# maus.net
KiCad netlist of a schematic drawn in EAGLE
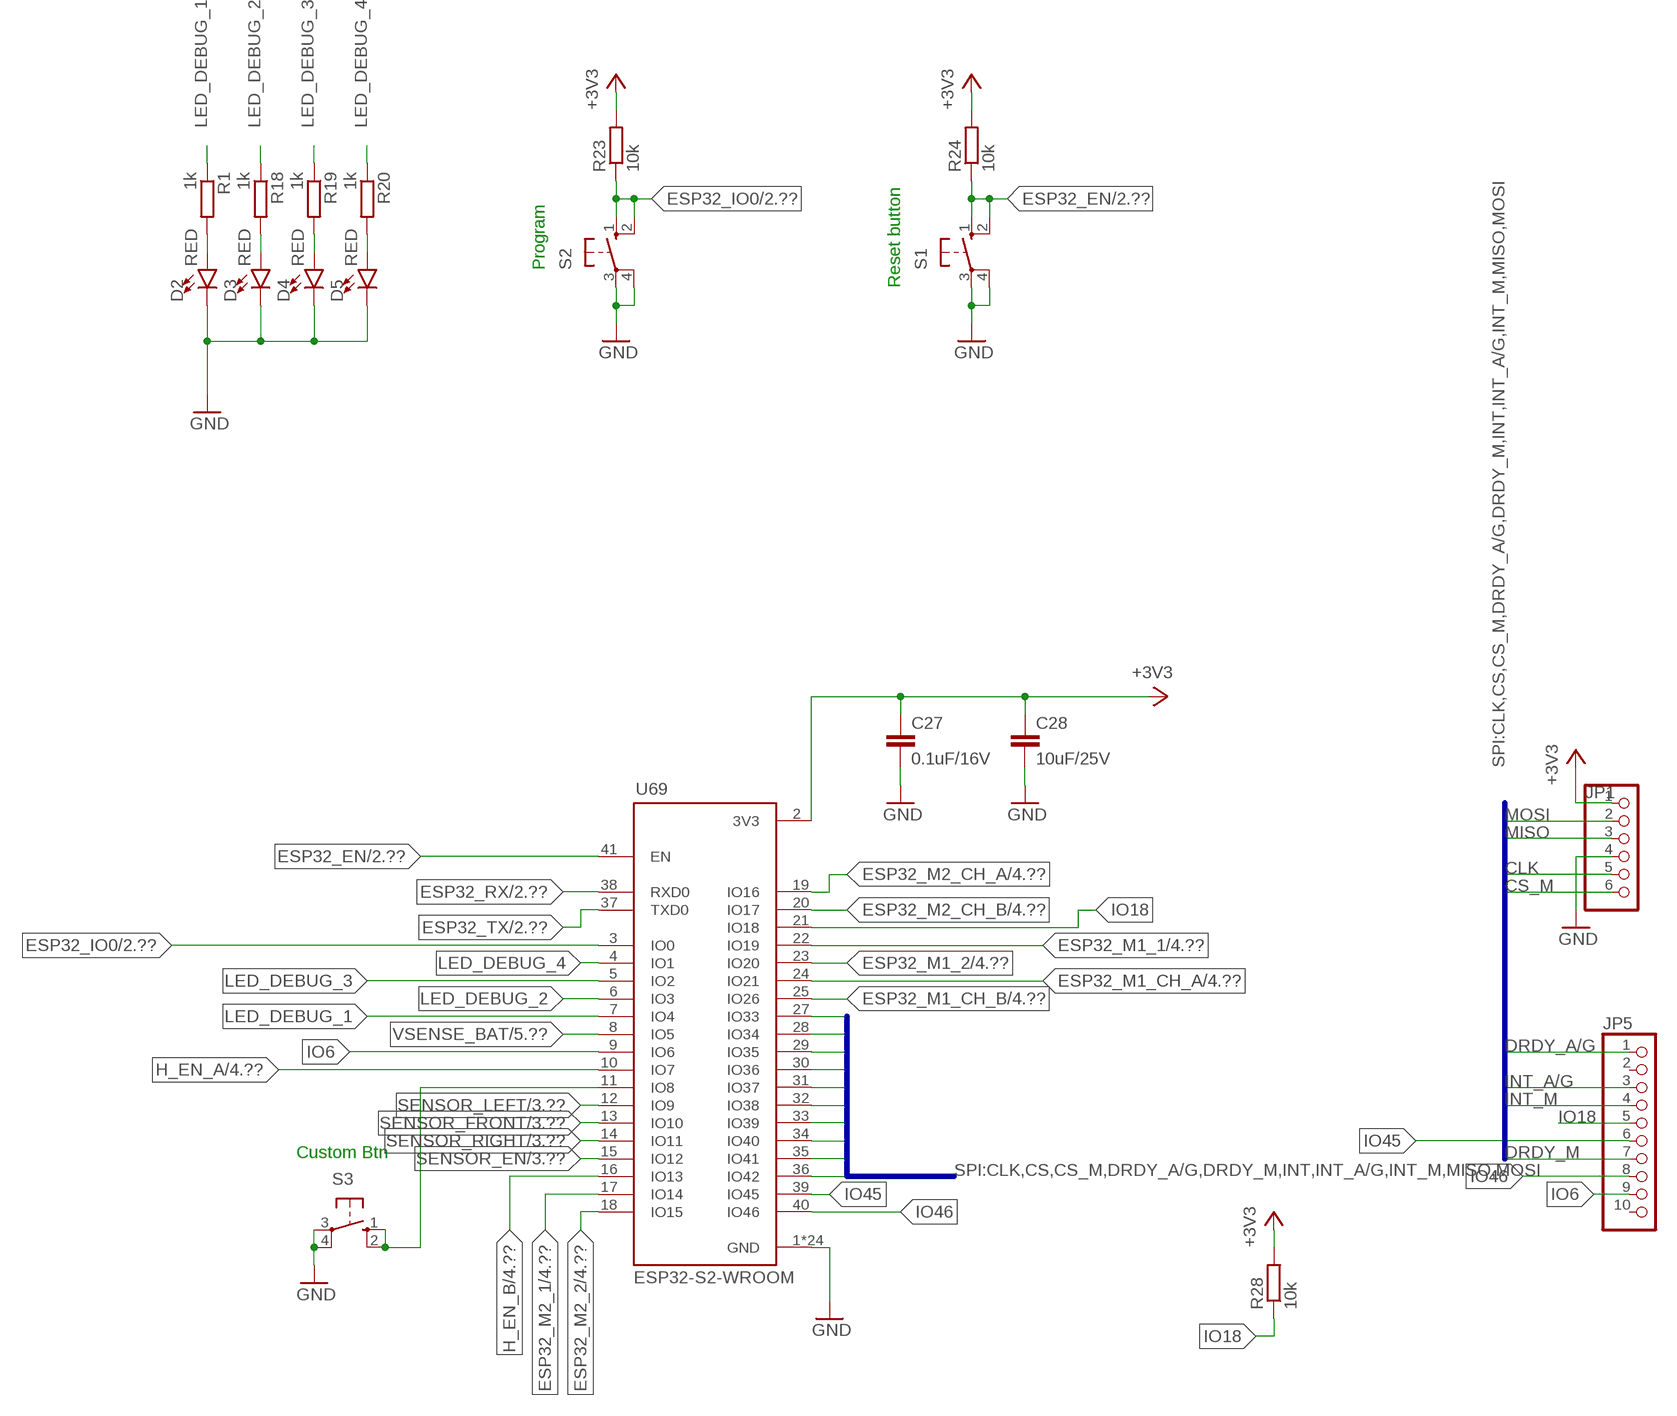
[diagram p0: schematic, sheet 1]
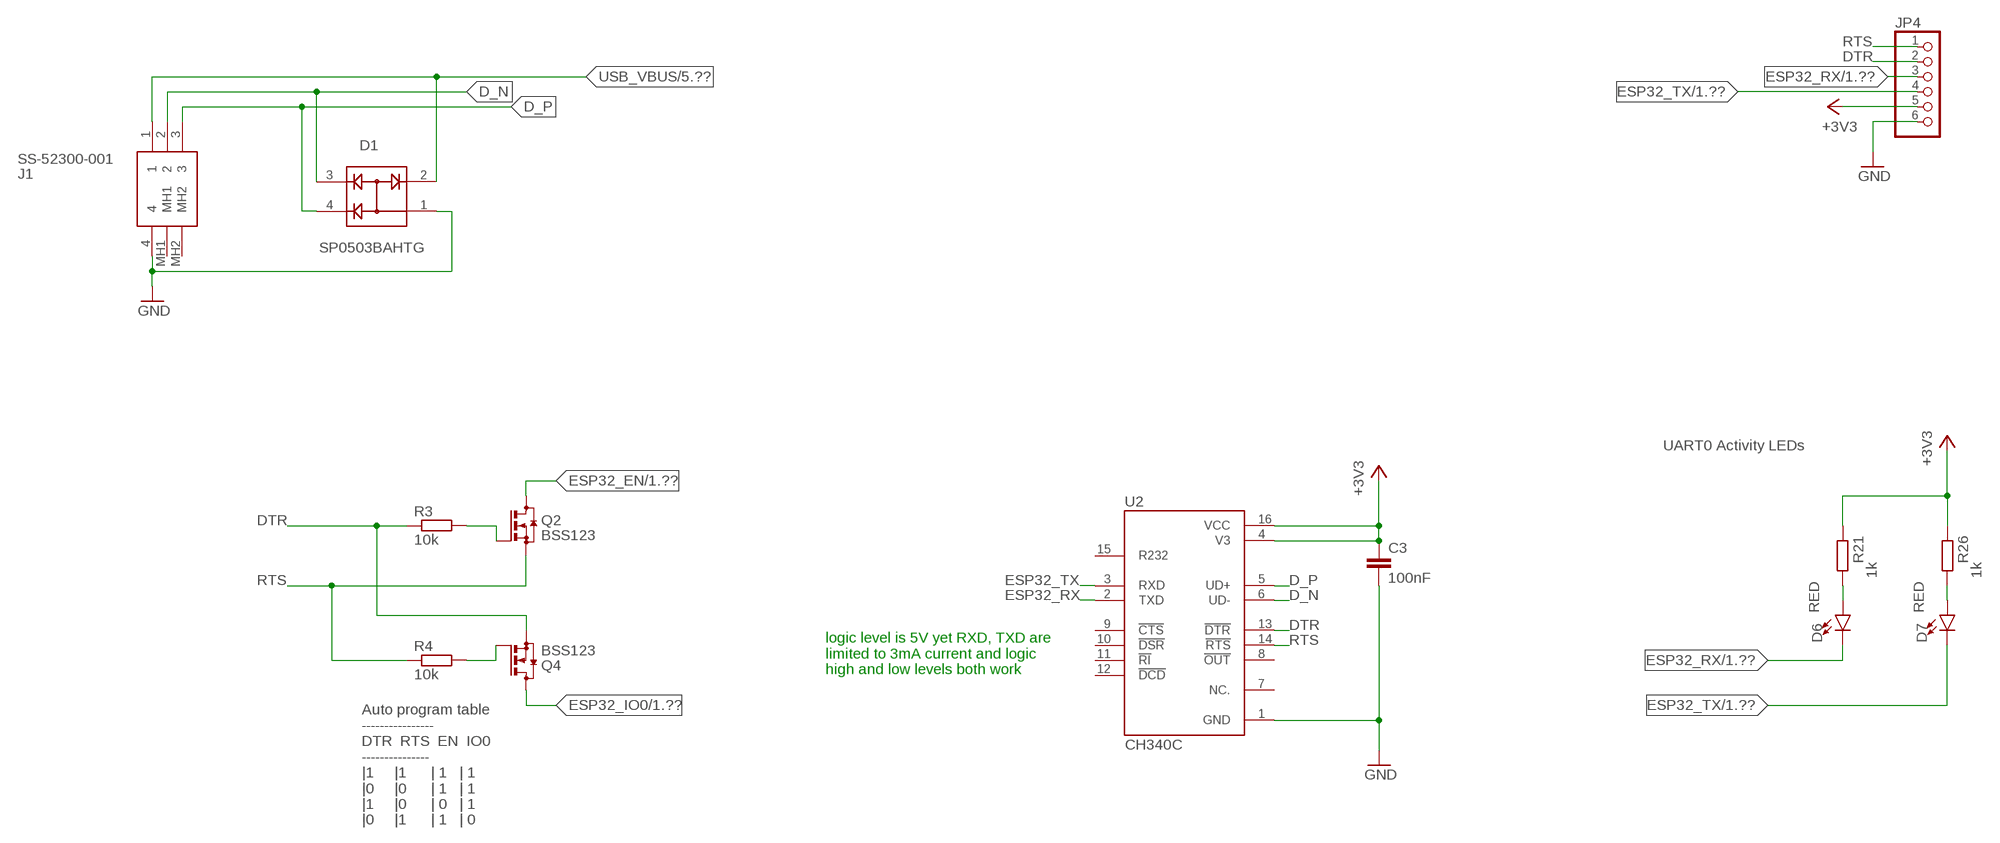
[diagram p1: schematic, sheet 2]
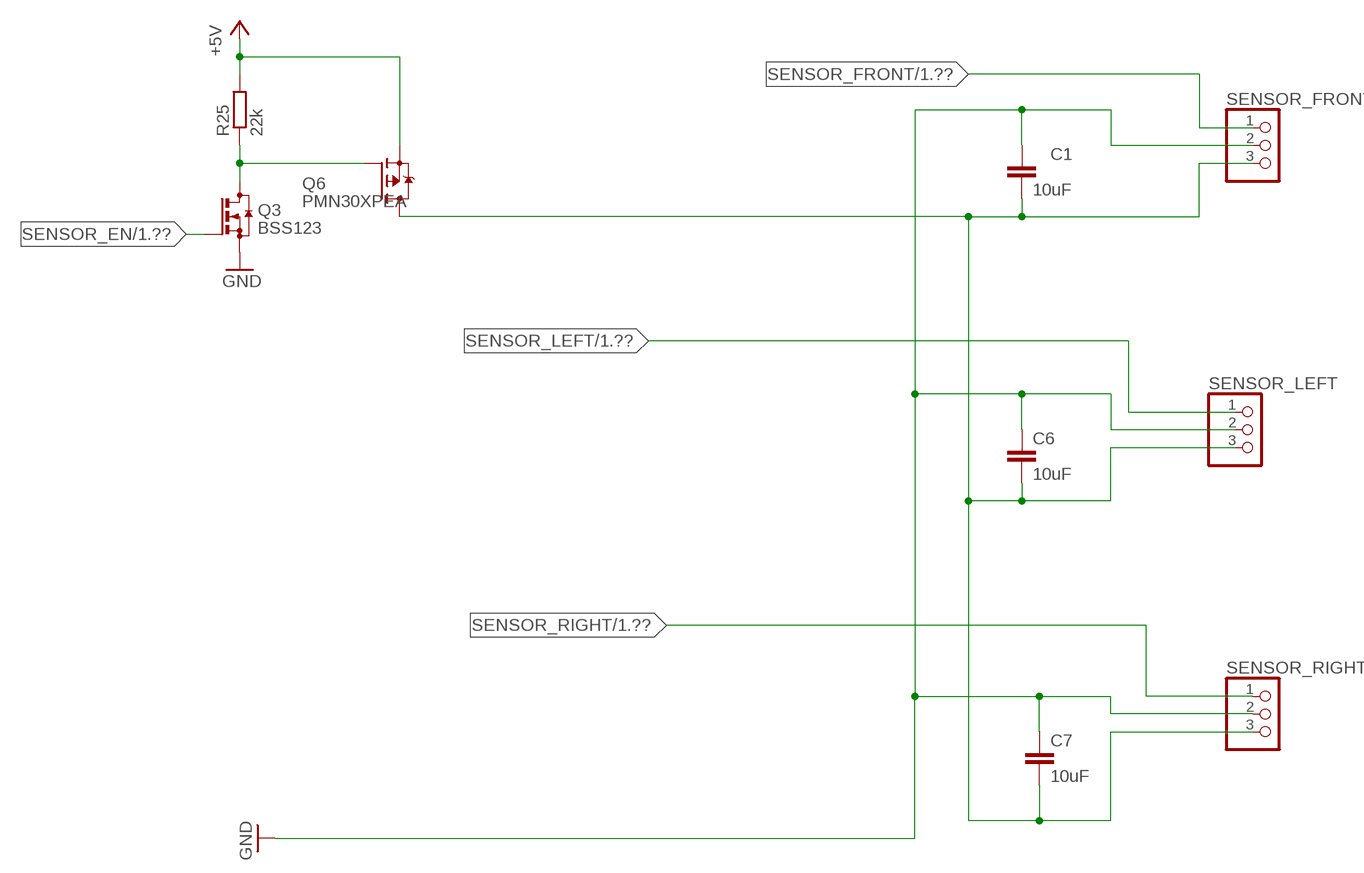
[diagram p2: schematic, sheet 3]
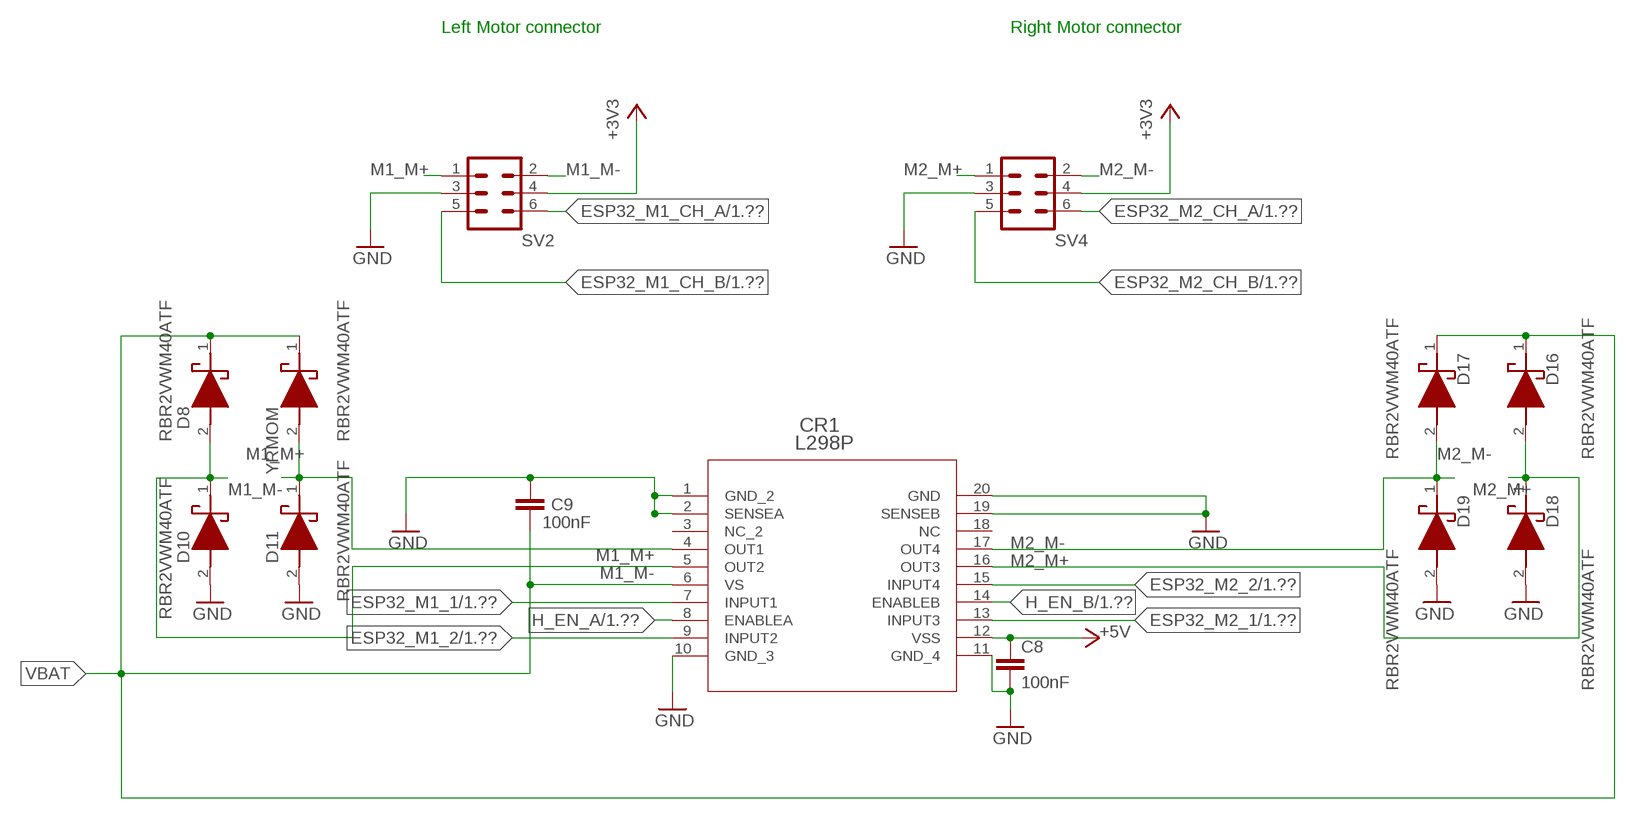
[diagram p3: schematic, sheet 4]
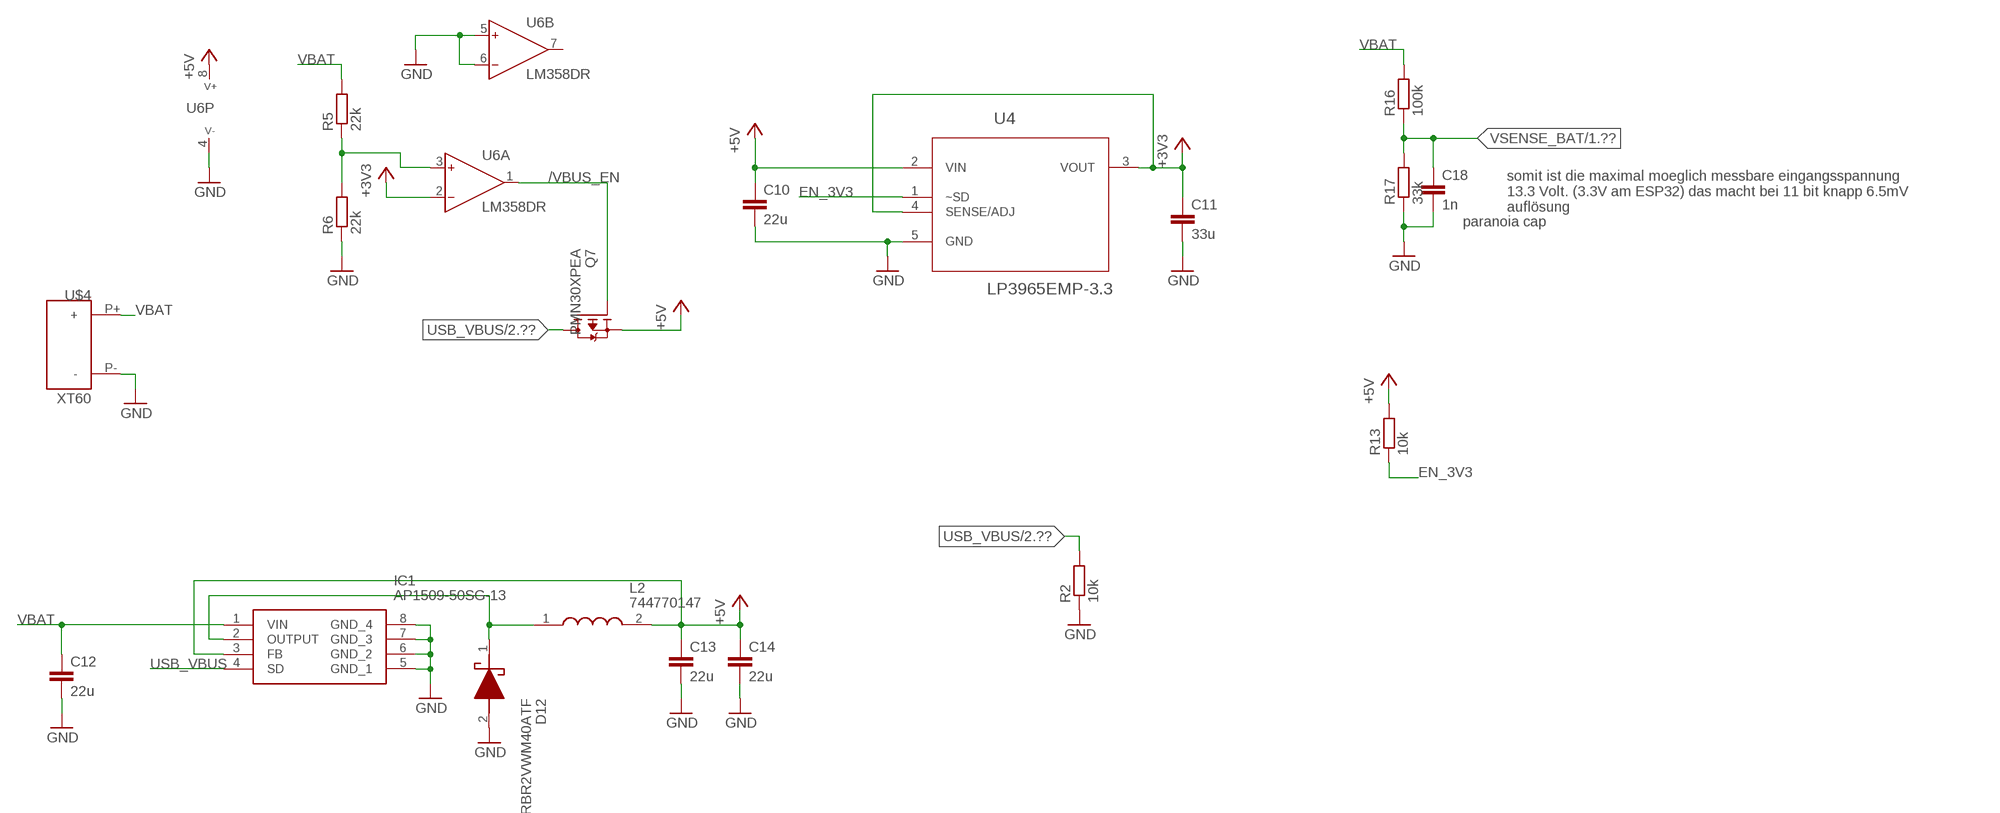
[diagram p4: schematic, sheet 5]
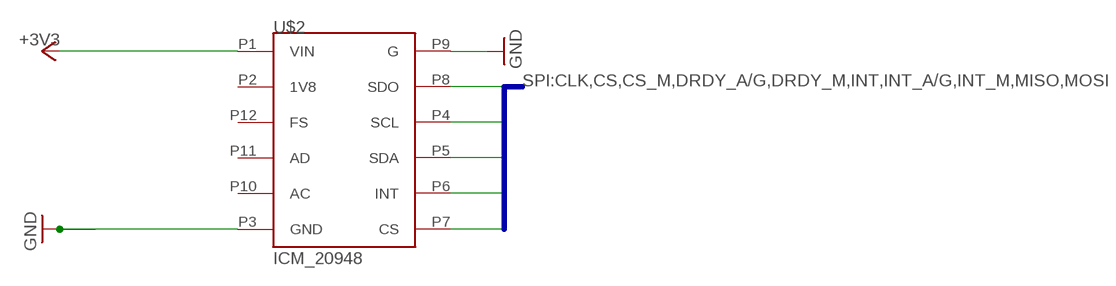
[diagram p5: schematic, sheet 6]

(export (version "E")
  (design (tool "Eeschema 10.0.6"))
  (components
    (comp (ref "C27")
      (value "0.1uF/16V")
      (footprint "eagle-import:C0805")
      (libsource (lib "eagle-import") (part "C-EUC0805"))
    )
    (comp (ref "C28")
      (value "10uF/25V")
      (footprint "eagle-import:C0805")
      (libsource (lib "eagle-import") (part "C-EUC0805"))
    )
    (comp (ref "D2")
      (value "RED")
      (footprint "eagle-import:LED-1206")
      (libsource (lib "eagle-import") (part "LED-RED1206"))
    )
    (comp (ref "D3")
      (value "RED")
      (footprint "eagle-import:LED-1206")
      (libsource (lib "eagle-import") (part "LED-RED1206"))
    )
    (comp (ref "D4")
      (value "RED")
      (footprint "eagle-import:LED-1206")
      (libsource (lib "eagle-import") (part "LED-RED1206"))
    )
    (comp (ref "D5")
      (value "RED")
      (footprint "eagle-import:LED-1206")
      (libsource (lib "eagle-import") (part "LED-RED1206"))
    )
    (comp (ref "JP1")
      (value "PINHD-1X6")
      (footprint "eagle-import:1X06")
      (libsource (lib "eagle-import") (part "PINHD-1X6"))
    )
    (comp (ref "JP5")
      (value "PINHD-1X10")
      (footprint "eagle-import:1X10")
      (libsource (lib "eagle-import") (part "PINHD-1X10"))
    )
    (comp (ref "R1")
      (value "1k")
      (footprint "eagle-import:R0805")
      (libsource (lib "eagle-import") (part "R-EU_R0805"))
    )
    (comp (ref "R18")
      (value "1k")
      (footprint "eagle-import:R0805")
      (libsource (lib "eagle-import") (part "R-EU_R0805"))
    )
    (comp (ref "R19")
      (value "1k")
      (footprint "eagle-import:R0805")
      (libsource (lib "eagle-import") (part "R-EU_R0805"))
    )
    (comp (ref "R20")
      (value "1k")
      (footprint "eagle-import:R0805")
      (libsource (lib "eagle-import") (part "R-EU_R0805"))
    )
    (comp (ref "R23")
      (value "10k")
      (footprint "eagle-import:R0805")
      (libsource (lib "eagle-import") (part "R-EU_R0805"))
    )
    (comp (ref "R24")
      (value "10k")
      (footprint "eagle-import:R0805")
      (libsource (lib "eagle-import") (part "R-EU_R0805"))
    )
    (comp (ref "R28")
      (value "10k")
      (footprint "eagle-import:R0805")
      (libsource (lib "eagle-import") (part "R-EU_R0805"))
    )
    (comp (ref "S1")
      (value "10-XX")
      (footprint "eagle-import:B3F-10XX")
      (fields (field (name "MPN") "B3F-1000"))
      (libsource (lib "eagle-import") (part "10-XX"))
    )
    (comp (ref "S2")
      (value "10-XX")
      (footprint "eagle-import:B3F-10XX")
      (fields (field (name "MPN") "B3F-1000"))
      (libsource (lib "eagle-import") (part "10-XX"))
    )
    (comp (ref "S3")
      (value "10-XX")
      (footprint "eagle-import:B3F-10XX")
      (fields (field (name "MPN") "B3F-1000"))
      (libsource (lib "eagle-import") (part "10-XX"))
    )
    (comp (ref "U69")
      (value "ESP32-S2-WROOM")
      (footprint "eagle-import:XCVR_ESP32-S2-WROOM")
      (fields (field (name "MF") "Espressif Systems"))
      (libsource (lib "eagle-import") (part "ESP32-S2-WROOM"))
    )
    (comp (ref "C8")
      (value "100nF")
      (footprint "eagle-import:C0805")
      (libsource (lib "eagle-import") (part "C-EUC0805"))
    )
    (comp (ref "C9")
      (value "100nF")
      (footprint "eagle-import:C0805")
      (libsource (lib "eagle-import") (part "C-EUC0805"))
    )
    (comp (ref "CR1")
      (value "L298P")
      (footprint "eagle-import:POWERSO-20_STM")
      (fields (field (name "COPYRIGHT") "Copyright (C) 2022 Ultra Librarian. All rights reserved."))
      (libsource (lib "eagle-import") (part "L298P"))
    )
    (comp (ref "D8")
      (value "RBR2VWM40ATF")
      (footprint "eagle-import:RB068VWM100")
      (libsource (lib "eagle-import") (part "RBR2VWM40ATF"))
    )
    (comp (ref "D10")
      (value "RBR2VWM40ATF")
      (footprint "eagle-import:RB068VWM100")
      (libsource (lib "eagle-import") (part "RBR2VWM40ATF"))
    )
    (comp (ref "D11")
      (value "RBR2VWM40ATF")
      (footprint "eagle-import:RB068VWM100")
      (libsource (lib "eagle-import") (part "RBR2VWM40ATF"))
    )
    (comp (ref "D16")
      (value "RBR2VWM40ATF")
      (footprint "eagle-import:RB068VWM100")
      (libsource (lib "eagle-import") (part "RBR2VWM40ATF"))
    )
    (comp (ref "D17")
      (value "RBR2VWM40ATF")
      (footprint "eagle-import:RB068VWM100")
      (libsource (lib "eagle-import") (part "RBR2VWM40ATF"))
    )
    (comp (ref "D18")
      (value "RBR2VWM40ATF")
      (footprint "eagle-import:RB068VWM100")
      (libsource (lib "eagle-import") (part "RBR2VWM40ATF"))
    )
    (comp (ref "D19")
      (value "RBR2VWM40ATF")
      (footprint "eagle-import:RB068VWM100")
      (libsource (lib "eagle-import") (part "RBR2VWM40ATF"))
    )
    (comp (ref "SV2")
      (value "ML6")
      (footprint "eagle-import:ML6")
      (libsource (lib "eagle-import") (part "ML6"))
    )
    (comp (ref "SV4")
      (value "ML6")
      (footprint "eagle-import:ML6")
      (libsource (lib "eagle-import") (part "ML6"))
    )
    (comp (ref "YRMOM")
      (value "RBR2VWM40ATF")
      (footprint "eagle-import:RB068VWM100")
      (libsource (lib "eagle-import") (part "RBR2VWM40ATF"))
    )
    (comp (ref "C3")
      (value "100nF")
      (footprint "eagle-import:C0805")
      (libsource (lib "eagle-import") (part "C-EUC0805"))
    )
    (comp (ref "D1")
      (value "SP0503BAHTG")
      (footprint "eagle-import:SOT143")
      (fields (field (name "MF") "Littelfuse Inc."))
      (libsource (lib "eagle-import") (part "SP0503BAHTG"))
    )
    (comp (ref "D6")
      (value "RED")
      (footprint "eagle-import:LED-1206")
      (libsource (lib "eagle-import") (part "LED-RED1206"))
    )
    (comp (ref "D7")
      (value "RED")
      (footprint "eagle-import:LED-1206")
      (libsource (lib "eagle-import") (part "LED-RED1206"))
    )
    (comp (ref "J1")
      (value "SS-52300-001")
      (footprint "eagle-import:SS52300001")
      (fields (field (name "MOUSER_PART_NUMBER") "530-SS-52300-001"))
      (libsource (lib "eagle-import") (part "SS-52300-001"))
    )
    (comp (ref "JP4")
      (value "PINHD-1X6")
      (footprint "eagle-import:1X06")
      (libsource (lib "eagle-import") (part "PINHD-1X6"))
    )
    (comp (ref "Q2")
      (value "BSS123")
      (footprint "eagle-import:SOT23")
      (libsource (lib "eagle-import") (part "BSS123"))
    )
    (comp (ref "Q4")
      (value "BSS123")
      (footprint "eagle-import:SOT23")
      (libsource (lib "eagle-import") (part "BSS123"))
    )
    (comp (ref "R3")
      (value "10k")
      (footprint "eagle-import:R0805")
      (libsource (lib "eagle-import") (part "R-EU_R0805"))
    )
    (comp (ref "R4")
      (value "10k")
      (footprint "eagle-import:R0805")
      (libsource (lib "eagle-import") (part "R-EU_R0805"))
    )
    (comp (ref "R21")
      (value "1k")
      (footprint "eagle-import:R0805")
      (libsource (lib "eagle-import") (part "R-EU_R0805"))
    )
    (comp (ref "R26")
      (value "1k")
      (footprint "eagle-import:R0805")
      (libsource (lib "eagle-import") (part "R-EU_R0805"))
    )
    (comp (ref "U2")
      (value "CH340C")
      (footprint "eagle-import:SOIC127P600X180-16N")
      (fields (field (name "MF") "WCH"))
      (libsource (lib "eagle-import") (part "CH340C"))
    )
    (comp (ref "C1")
      (value "10uF")
      (footprint "eagle-import:C0805")
      (libsource (lib "eagle-import") (part "C-EUC0805"))
    )
    (comp (ref "C6")
      (value "10uF")
      (footprint "eagle-import:C0805")
      (libsource (lib "eagle-import") (part "C-EUC0805"))
    )
    (comp (ref "C7")
      (value "10uF")
      (footprint "eagle-import:C0805")
      (libsource (lib "eagle-import") (part "C-EUC0805"))
    )
    (comp (ref "Q3")
      (value "BSS123")
      (footprint "eagle-import:SOT23")
      (libsource (lib "eagle-import") (part "BSS123"))
    )
    (comp (ref "Q6")
      (value "PMN30XPEA")
      (footprint "eagle-import:SOT95P255X110-6N")
      (libsource (lib "eagle-import") (part "PMN30XPEA"))
    )
    (comp (ref "R25")
      (value "22k")
      (footprint "eagle-import:R0805")
      (libsource (lib "eagle-import") (part "R-EU_R0805"))
    )
    (comp (ref "SENSOR_FRONT")
      (value "PINHD-1X3")
      (footprint "eagle-import:1X03")
      (libsource (lib "eagle-import") (part "PINHD-1X3"))
    )
    (comp (ref "SENSOR_LEFT")
      (value "PINHD-1X3")
      (footprint "eagle-import:1X03")
      (libsource (lib "eagle-import") (part "PINHD-1X3"))
    )
    (comp (ref "SENSOR_RIGHT")
      (value "PINHD-1X3")
      (footprint "eagle-import:1X03")
      (libsource (lib "eagle-import") (part "PINHD-1X3"))
    )
    (comp (ref "C10")
      (value "22u")
      (footprint "eagle-import:C0805")
      (libsource (lib "eagle-import") (part "C-EUC0805"))
    )
    (comp (ref "C11")
      (value "33u")
      (footprint "eagle-import:C0805")
      (libsource (lib "eagle-import") (part "C-EUC0805"))
    )
    (comp (ref "C12")
      (value "22u")
      (footprint "eagle-import:C0805")
      (libsource (lib "eagle-import") (part "C-EUC0805"))
    )
    (comp (ref "C13")
      (value "22u")
      (footprint "eagle-import:C0805")
      (libsource (lib "eagle-import") (part "C-EUC0805"))
    )
    (comp (ref "C14")
      (value "22u")
      (footprint "eagle-import:C0805")
      (libsource (lib "eagle-import") (part "C-EUC0805"))
    )
    (comp (ref "C18")
      (value "1n")
      (footprint "eagle-import:C0805")
      (libsource (lib "eagle-import") (part "C-EUC0805"))
    )
    (comp (ref "D12")
      (value "RBR2VWM40ATF")
      (footprint "eagle-import:RB068VWM100")
      (libsource (lib "eagle-import") (part "RBR2VWM40ATF"))
    )
    (comp (ref "IC1")
      (value "AP1509-50SG-13")
      (footprint "eagle-import:SOIC127P600X175-8N")
      (fields (field (name "MOUSER_PART_NUMBER") "621-AP1509-50SG-13"))
      (libsource (lib "eagle-import") (part "AP1509-50SG-13"))
    )
    (comp (ref "L2")
      (value "744770147")
      (footprint "eagle-import:WE-PD_1260_1245_1280_121054")
      (fields (field (name "MOUSER_PART_NUMBER") "710-744770147"))
      (libsource (lib "eagle-import") (part "744770147"))
    )
    (comp (ref "Q7")
      (value "PMN30XPEA")
      (footprint "eagle-import:SOT95P255X110-6N")
      (libsource (lib "eagle-import") (part "PMN30XPEA"))
    )
    (comp (ref "R2")
      (value "10k")
      (footprint "eagle-import:R0805")
      (libsource (lib "eagle-import") (part "R-EU_R0805"))
    )
    (comp (ref "R5")
      (value "22k")
      (footprint "eagle-import:R0805")
      (libsource (lib "eagle-import") (part "R-EU_R0805"))
    )
    (comp (ref "R6")
      (value "22k")
      (footprint "eagle-import:R0805")
      (libsource (lib "eagle-import") (part "R-EU_R0805"))
    )
    (comp (ref "R13")
      (value "10k")
      (footprint "eagle-import:R0805")
      (libsource (lib "eagle-import") (part "R-EU_R0805"))
    )
    (comp (ref "R16")
      (value "100k")
      (footprint "eagle-import:R0805")
      (libsource (lib "eagle-import") (part "R-EU_R0805"))
    )
    (comp (ref "R17")
      (value "33k")
      (footprint "eagle-import:R0805")
      (libsource (lib "eagle-import") (part "R-EU_R0805"))
    )
    (comp (ref "U$4")
      (value "XT60")
      (footprint "eagle-import:XT60-UPRIGHT")
      (libsource (lib "eagle-import") (part "XT60"))
    )
    (comp (ref "U4")
      (value "LP3965EMP-3.3")
      (footprint "eagle-import:SOT150P696X180-5N")
      (fields (field (name "MF") "Texas Instruments") (field (name "MP") "LP3965EMP-3.3/NOPB"))
      (libsource (lib "eagle-import") (part "LP3965EMP-3.3"))
    )
    (comp (ref "U6")
      (value "LM358DR")
      (footprint "eagle-import:SOIC127P610X175-8N")
      (libsource (lib "eagle-import") (part "LM358DR"))
    )
    (comp (ref "U$2")
      (value "ICM_20948")
      (footprint "eagle-import:ICM_20948-F")
      (libsource (lib "eagle-import") (part "ICM_20948"))
    )
  )
  (nets
    (net (code "8") (name "+3V3") (class "Default")
      (node (ref "C11") (pin "1") (pinfunction "1_1") (pintype "passive"))
      (node (ref "C27") (pin "1") (pinfunction "1_1") (pintype "passive"))
      (node (ref "C28") (pin "1") (pinfunction "1_1") (pintype "passive"))
      (node (ref "C3") (pin "1") (pinfunction "1_1") (pintype "passive"))
      (node (ref "JP1") (pin "1") (pinfunction "1_1") (pintype "passive"))
      (node (ref "JP4") (pin "5") (pinfunction "5_5") (pintype "passive"))
      (node (ref "R21") (pin "2") (pinfunction "2_2") (pintype "passive"))
      (node (ref "R23") (pin "2") (pinfunction "2_2") (pintype "passive"))
      (node (ref "R24") (pin "2") (pinfunction "2_2") (pintype "passive"))
      (node (ref "R26") (pin "2") (pinfunction "2_2") (pintype "passive"))
      (node (ref "R28") (pin "2") (pinfunction "2_2") (pintype "passive"))
      (node (ref "SV2") (pin "4") (pinfunction "4_4") (pintype "passive"))
      (node (ref "SV4") (pin "4") (pinfunction "4_4") (pintype "passive"))
      (node (ref "U$2") (pin "P1") (pinfunction "VIN_P1") (pintype "bidirectional"))
      (node (ref "U2") (pin "16") (pinfunction "VCC_16") (pintype "power_in"))
      (node (ref "U2") (pin "4") (pinfunction "V3_4") (pintype "power_in"))
      (node (ref "U4") (pin "3") (pinfunction "VOUT_3") (pintype "passive"))
      (node (ref "U4") (pin "4") (pinfunction "SENSE/ADJ_4") (pintype "input"))
      (node (ref "U6") (pin "2") (pinfunction "IN-_2") (pintype "input"))
      (node (ref "U69") (pin "2") (pinfunction "3V3_2") (pintype "power_in"))
    )
    (net (code "9") (name "+5V") (class "Default")
      (node (ref "C10") (pin "1") (pinfunction "1_1") (pintype "passive"))
      (node (ref "C13") (pin "1") (pinfunction "1_1") (pintype "passive"))
      (node (ref "C14") (pin "1") (pinfunction "1_1") (pintype "passive"))
      (node (ref "C8") (pin "1") (pinfunction "1_1") (pintype "passive"))
      (node (ref "CR1") (pin "12") (pinfunction "VSS_12") (pintype "power_in"))
      (node (ref "IC1") (pin "3") (pinfunction "FB_3") (pintype "bidirectional"))
      (node (ref "L2") (pin "2") (pinfunction "2_2") (pintype "bidirectional"))
      (node (ref "Q6") (pin "4") (pinfunction "S_4") (pintype "passive"))
      (node (ref "Q7") (pin "4") (pinfunction "S_4") (pintype "passive"))
      (node (ref "R13") (pin "2") (pinfunction "2_2") (pintype "passive"))
      (node (ref "R25") (pin "2") (pinfunction "2_2") (pintype "passive"))
      (node (ref "U4") (pin "2") (pinfunction "VIN_2") (pintype "input"))
      (node (ref "U6") (pin "8") (pinfunction "V+_8") (pintype "power_in"))
    )
    (net (code "12") (name "CLK") (class "Default")
      (node (ref "JP1") (pin "5") (pinfunction "5_5") (pintype "passive"))
      (node (ref "U$2") (pin "P4") (pinfunction "SCL_P4") (pintype "bidirectional"))
      (node (ref "U69") (pin "30") (pinfunction "IO36_30") (pintype "bidirectional"))
    )
    (net (code "13") (name "CS") (class "Default")
      (node (ref "U$2") (pin "P7") (pinfunction "CS_P7") (pintype "bidirectional"))
      (node (ref "U69") (pin "28") (pinfunction "IO34_28") (pintype "bidirectional"))
    )
    (net (code "14") (name "CS_M") (class "Default")
      (node (ref "JP1") (pin "6") (pinfunction "6_6") (pintype "passive"))
      (node (ref "U69") (pin "27") (pinfunction "IO33_27") (pintype "bidirectional"))
    )
    (net (code "15") (name "DRDY_A{slash}G") (class "Default")
      (node (ref "JP5") (pin "1") (pinfunction "1_1") (pintype "passive"))
      (node (ref "U69") (pin "36") (pinfunction "IO42_36") (pintype "bidirectional"))
    )
    (net (code "16") (name "DRDY_M") (class "Default")
      (node (ref "JP5") (pin "7") (pinfunction "7_7") (pintype "passive"))
      (node (ref "U69") (pin "32") (pinfunction "IO38_32") (pintype "bidirectional"))
    )
    (net (code "17") (name "DTR") (class "Default")
      (node (ref "JP4") (pin "2") (pinfunction "2_2") (pintype "passive"))
      (node (ref "Q4") (pin "2") (pinfunction "S_2") (pintype "passive"))
      (node (ref "R3") (pin "1") (pinfunction "1_1") (pintype "passive"))
      (node (ref "U2") (pin "13") (pinfunction "~{DTR}_13") (pintype "output"))
    )
    (net (code "18") (name "D_N") (class "Default")
      (node (ref "D1") (pin "3") (pinfunction "3_3") (pintype "passive"))
      (node (ref "J1") (pin "2") (pinfunction "2_2") (pintype "bidirectional"))
      (node (ref "U2") (pin "6") (pinfunction "UD-_6") (pintype "bidirectional"))
    )
    (net (code "19") (name "D_P") (class "Default")
      (node (ref "D1") (pin "4") (pinfunction "4_4") (pintype "passive"))
      (node (ref "J1") (pin "3") (pinfunction "3_3") (pintype "bidirectional"))
      (node (ref "U2") (pin "5") (pinfunction "UD+_5") (pintype "bidirectional"))
    )
    (net (code "20") (name "EN_3V3") (class "Default")
      (node (ref "R13") (pin "1") (pinfunction "1_1") (pintype "passive"))
      (node (ref "U4") (pin "1") (pinfunction "~{SD}_1") (pintype "input"))
    )
    (net (code "21") (name "ESP32_EN") (class "Default")
      (node (ref "Q2") (pin "3") (pinfunction "D_3") (pintype "passive"))
      (node (ref "R24") (pin "1") (pinfunction "1_1") (pintype "passive"))
      (node (ref "S1") (pin "1") (pinfunction "S_1") (pintype "passive"))
      (node (ref "S1") (pin "2") (pinfunction "S1_2") (pintype "passive"))
      (node (ref "U69") (pin "41") (pinfunction "EN_41") (pintype "input"))
    )
    (net (code "22") (name "ESP32_IO0") (class "Default")
      (node (ref "Q4") (pin "3") (pinfunction "D_3") (pintype "passive"))
      (node (ref "R23") (pin "1") (pinfunction "1_1") (pintype "passive"))
      (node (ref "S2") (pin "1") (pinfunction "S_1") (pintype "passive"))
      (node (ref "S2") (pin "2") (pinfunction "S1_2") (pintype "passive"))
      (node (ref "U69") (pin "3") (pinfunction "IO0_3") (pintype "bidirectional"))
    )
    (net (code "23") (name "ESP32_M1_1") (class "Default")
      (node (ref "CR1") (pin "7") (pinfunction "INPUT1_7") (pintype "input"))
      (node (ref "U69") (pin "22") (pinfunction "IO19_22") (pintype "bidirectional"))
    )
    (net (code "24") (name "ESP32_M1_2") (class "Default")
      (node (ref "CR1") (pin "9") (pinfunction "INPUT2_9") (pintype "input"))
      (node (ref "U69") (pin "23") (pinfunction "IO20_23") (pintype "bidirectional"))
    )
    (net (code "25") (name "ESP32_M1_CH_A") (class "Default")
      (node (ref "SV2") (pin "6") (pinfunction "6_6") (pintype "passive"))
      (node (ref "U69") (pin "24") (pinfunction "IO21_24") (pintype "bidirectional"))
    )
    (net (code "26") (name "ESP32_M1_CH_B") (class "Default")
      (node (ref "SV2") (pin "5") (pinfunction "5_5") (pintype "passive"))
      (node (ref "U69") (pin "25") (pinfunction "IO26_25") (pintype "bidirectional"))
    )
    (net (code "27") (name "ESP32_M2_1") (class "Default")
      (node (ref "CR1") (pin "13") (pinfunction "INPUT3_13") (pintype "input"))
      (node (ref "U69") (pin "17") (pinfunction "IO14_17") (pintype "bidirectional"))
    )
    (net (code "28") (name "ESP32_M2_2") (class "Default")
      (node (ref "CR1") (pin "15") (pinfunction "INPUT4_15") (pintype "input"))
      (node (ref "U69") (pin "18") (pinfunction "IO15_18") (pintype "bidirectional"))
    )
    (net (code "29") (name "ESP32_M2_CH_A") (class "Default")
      (node (ref "SV4") (pin "6") (pinfunction "6_6") (pintype "passive"))
      (node (ref "U69") (pin "19") (pinfunction "IO16_19") (pintype "bidirectional"))
    )
    (net (code "30") (name "ESP32_M2_CH_B") (class "Default")
      (node (ref "SV4") (pin "5") (pinfunction "5_5") (pintype "passive"))
      (node (ref "U69") (pin "20") (pinfunction "IO17_20") (pintype "bidirectional"))
    )
    (net (code "31") (name "ESP32_RX") (class "Default")
      (node (ref "D6") (pin "C") (pinfunction "C_C") (pintype "passive"))
      (node (ref "JP4") (pin "3") (pinfunction "3_3") (pintype "passive"))
      (node (ref "U2") (pin "2") (pinfunction "TXD_2") (pintype "output"))
      (node (ref "U69") (pin "38") (pinfunction "RXD0_38") (pintype "bidirectional"))
    )
    (net (code "32") (name "ESP32_TX") (class "Default")
      (node (ref "D7") (pin "C") (pinfunction "C_C") (pintype "passive"))
      (node (ref "JP4") (pin "4") (pinfunction "4_4") (pintype "passive"))
      (node (ref "U2") (pin "3") (pinfunction "RXD_3") (pintype "input"))
      (node (ref "U69") (pin "37") (pinfunction "TXD0_37") (pintype "bidirectional"))
    )
    (net (code "33") (name "GND") (class "Default")
      (node (ref "C1") (pin "1") (pinfunction "1_1") (pintype "passive"))
      (node (ref "C10") (pin "2") (pinfunction "2_2") (pintype "passive"))
      (node (ref "C11") (pin "2") (pinfunction "2_2") (pintype "passive"))
      (node (ref "C12") (pin "2") (pinfunction "2_2") (pintype "passive"))
      (node (ref "C13") (pin "2") (pinfunction "2_2") (pintype "passive"))
      (node (ref "C14") (pin "2") (pinfunction "2_2") (pintype "passive"))
      (node (ref "C18") (pin "2") (pinfunction "2_2") (pintype "passive"))
      (node (ref "C27") (pin "2") (pinfunction "2_2") (pintype "passive"))
      (node (ref "C28") (pin "2") (pinfunction "2_2") (pintype "passive"))
      (node (ref "C3") (pin "2") (pinfunction "2_2") (pintype "passive"))
      (node (ref "C6") (pin "1") (pinfunction "1_1") (pintype "passive"))
      (node (ref "C7") (pin "1") (pinfunction "1_1") (pintype "passive"))
      (node (ref "C8") (pin "2") (pinfunction "2_2") (pintype "passive"))
      (node (ref "C9") (pin "2") (pinfunction "2_2") (pintype "passive"))
      (node (ref "CR1") (pin "1") (pinfunction "GND_2_1") (pintype "passive"))
      (node (ref "CR1") (pin "10") (pinfunction "GND_3_10") (pintype "passive"))
      (node (ref "CR1") (pin "11") (pinfunction "GND_4_11") (pintype "passive"))
      (node (ref "CR1") (pin "19") (pinfunction "SENSEB_19") (pintype "input"))
      (node (ref "CR1") (pin "2") (pinfunction "SENSEA_2") (pintype "input"))
      (node (ref "CR1") (pin "20") (pinfunction "GND_20") (pintype "passive"))
      (node (ref "D1") (pin "1") (pinfunction "1_1") (pintype "passive"))
      (node (ref "D10") (pin "2") (pinfunction "A_2") (pintype "bidirectional"))
      (node (ref "D11") (pin "2") (pinfunction "A_2") (pintype "bidirectional"))
      (node (ref "D12") (pin "2") (pinfunction "A_2") (pintype "bidirectional"))
      (node (ref "D18") (pin "2") (pinfunction "A_2") (pintype "bidirectional"))
      (node (ref "D19") (pin "2") (pinfunction "A_2") (pintype "bidirectional"))
      (node (ref "D2") (pin "C") (pinfunction "C_C") (pintype "passive"))
      (node (ref "D3") (pin "C") (pinfunction "C_C") (pintype "passive"))
      (node (ref "D4") (pin "C") (pinfunction "C_C") (pintype "passive"))
      (node (ref "D5") (pin "C") (pinfunction "C_C") (pintype "passive"))
      (node (ref "IC1") (pin "5") (pinfunction "GND_1_5") (pintype "bidirectional"))
      (node (ref "IC1") (pin "6") (pinfunction "GND_2_6") (pintype "bidirectional"))
      (node (ref "IC1") (pin "7") (pinfunction "GND_3_7") (pintype "bidirectional"))
      (node (ref "IC1") (pin "8") (pinfunction "GND_4_8") (pintype "bidirectional"))
      (node (ref "J1") (pin "4") (pinfunction "4_4") (pintype "bidirectional"))
      (node (ref "JP1") (pin "4") (pinfunction "4_4") (pintype "passive"))
      (node (ref "JP4") (pin "6") (pinfunction "6_6") (pintype "passive"))
      (node (ref "Q3") (pin "2") (pinfunction "S_2") (pintype "passive"))
      (node (ref "R17") (pin "1") (pinfunction "1_1") (pintype "passive"))
      (node (ref "R2") (pin "1") (pinfunction "1_1") (pintype "passive"))
      (node (ref "R6") (pin "1") (pinfunction "1_1") (pintype "passive"))
      (node (ref "S1") (pin "3") (pinfunction "P_3") (pintype "passive"))
      (node (ref "S1") (pin "4") (pinfunction "P1_4") (pintype "passive"))
      (node (ref "S2") (pin "3") (pinfunction "P_3") (pintype "passive"))
      (node (ref "S2") (pin "4") (pinfunction "P1_4") (pintype "passive"))
      (node (ref "S3") (pin "3") (pinfunction "P_3") (pintype "passive"))
      (node (ref "S3") (pin "4") (pinfunction "P1_4") (pintype "passive"))
      (node (ref "SENSOR_FRONT") (pin "2") (pinfunction "2_2") (pintype "passive"))
      (node (ref "SENSOR_LEFT") (pin "2") (pinfunction "2_2") (pintype "passive"))
      (node (ref "SENSOR_RIGHT") (pin "2") (pinfunction "2_2") (pintype "passive"))
      (node (ref "SV2") (pin "3") (pinfunction "3_3") (pintype "passive"))
      (node (ref "SV4") (pin "3") (pinfunction "3_3") (pintype "passive"))
      (node (ref "U$2") (pin "P3") (pinfunction "GND_P3") (pintype "bidirectional"))
      (node (ref "U$2") (pin "P9") (pinfunction "G_P9") (pintype "bidirectional"))
      (node (ref "U$4") (pin "P-") (pinfunction "-_P-") (pintype "passive"))
      (node (ref "U2") (pin "1") (pinfunction "GND_1") (pintype "power_in"))
      (node (ref "U4") (pin "5") (pinfunction "GND_5") (pintype "input"))
      (node (ref "U6") (pin "4") (pinfunction "V-_4") (pintype "power_in"))
      (node (ref "U6") (pin "5") (pinfunction "IN+_5") (pintype "input"))
      (node (ref "U6") (pin "6") (pinfunction "IN-_6") (pintype "input"))
      (node (ref "U69") (pin "1") (pinfunction "GND_1") (pintype "power_in"))
      (node (ref "U69") (pin "26") (pinfunction "GND_26") (pintype "power_in"))
      (node (ref "U69") (pin "42") (pinfunction "GND_42") (pintype "power_in"))
      (node (ref "U69") (pin "43.1") (pinfunction "GND_43.1") (pintype "power_in"))
      (node (ref "U69") (pin "43.10") (pinfunction "GND_43.10") (pintype "power_in"))
      (node (ref "U69") (pin "43.11") (pinfunction "GND_43.11") (pintype "power_in"))
      (node (ref "U69") (pin "43.12") (pinfunction "GND_43.12") (pintype "power_in"))
      (node (ref "U69") (pin "43.13") (pinfunction "GND_43.13") (pintype "power_in"))
      (node (ref "U69") (pin "43.14") (pinfunction "GND_43.14") (pintype "power_in"))
      (node (ref "U69") (pin "43.15") (pinfunction "GND_43.15") (pintype "power_in"))
      (node (ref "U69") (pin "43.16") (pinfunction "GND_43.16") (pintype "power_in"))
      (node (ref "U69") (pin "43.17") (pinfunction "GND_43.17") (pintype "power_in"))
      (node (ref "U69") (pin "43.18") (pinfunction "GND_43.18") (pintype "power_in"))
      (node (ref "U69") (pin "43.19") (pinfunction "GND_43.19") (pintype "power_in"))
      (node (ref "U69") (pin "43.2") (pinfunction "GND_43.2") (pintype "power_in"))
      (node (ref "U69") (pin "43.20") (pinfunction "GND_43.20") (pintype "power_in"))
      (node (ref "U69") (pin "43.21") (pinfunction "GND_43.21") (pintype "power_in"))
      (node (ref "U69") (pin "43.3") (pinfunction "GND_43.3") (pintype "power_in"))
      (node (ref "U69") (pin "43.4") (pinfunction "GND_43.4") (pintype "power_in"))
      (node (ref "U69") (pin "43.5") (pinfunction "GND_43.5") (pintype "power_in"))
      (node (ref "U69") (pin "43.6") (pinfunction "GND_43.6") (pintype "power_in"))
      (node (ref "U69") (pin "43.7") (pinfunction "GND_43.7") (pintype "power_in"))
      (node (ref "U69") (pin "43.8") (pinfunction "GND_43.8") (pintype "power_in"))
      (node (ref "U69") (pin "43.9") (pinfunction "GND_43.9") (pintype "power_in"))
    )
    (net (code "34") (name "H_EN_A") (class "Default")
      (node (ref "CR1") (pin "8") (pinfunction "ENABLEA_8") (pintype "input"))
      (node (ref "U69") (pin "10") (pinfunction "IO7_10") (pintype "bidirectional"))
    )
    (net (code "35") (name "H_EN_B") (class "Default")
      (node (ref "CR1") (pin "14") (pinfunction "ENABLEB_14") (pintype "input"))
      (node (ref "U69") (pin "16") (pinfunction "IO13_16") (pintype "bidirectional"))
    )
    (net (code "36") (name "INT") (class "Default")
      (node (ref "U$2") (pin "P6") (pinfunction "INT_P6") (pintype "bidirectional"))
      (node (ref "U69") (pin "33") (pinfunction "IO39_33") (pintype "bidirectional"))
    )
    (net (code "37") (name "INT_A{slash}G") (class "Default")
      (node (ref "JP5") (pin "3") (pinfunction "3_3") (pintype "passive"))
      (node (ref "U69") (pin "35") (pinfunction "IO41_35") (pintype "bidirectional"))
    )
    (net (code "38") (name "INT_M") (class "Default")
      (node (ref "JP5") (pin "4") (pinfunction "4_4") (pintype "passive"))
      (node (ref "U69") (pin "34") (pinfunction "IO40_34") (pintype "bidirectional"))
    )
    (net (code "39") (name "IO6") (class "Default")
      (node (ref "JP5") (pin "9") (pinfunction "9_9") (pintype "passive"))
      (node (ref "U69") (pin "9") (pinfunction "IO6_9") (pintype "bidirectional"))
    )
    (net (code "40") (name "IO18") (class "Default")
      (node (ref "JP5") (pin "5") (pinfunction "5_5") (pintype "passive"))
      (node (ref "R28") (pin "1") (pinfunction "1_1") (pintype "passive"))
      (node (ref "U69") (pin "21") (pinfunction "IO18_21") (pintype "bidirectional"))
    )
    (net (code "41") (name "IO45") (class "Default")
      (node (ref "JP5") (pin "6") (pinfunction "6_6") (pintype "passive"))
      (node (ref "U69") (pin "39") (pinfunction "IO45_39") (pintype "bidirectional"))
    )
    (net (code "42") (name "IO46") (class "Default")
      (node (ref "JP5") (pin "8") (pinfunction "8_8") (pintype "passive"))
      (node (ref "U69") (pin "40") (pinfunction "IO46_40") (pintype "bidirectional"))
    )
    (net (code "43") (name "LED_DEBUG_1") (class "Default")
      (node (ref "R1") (pin "1") (pinfunction "1_1") (pintype "passive"))
      (node (ref "U69") (pin "7") (pinfunction "IO4_7") (pintype "bidirectional"))
    )
    (net (code "44") (name "LED_DEBUG_2") (class "Default")
      (node (ref "R18") (pin "1") (pinfunction "1_1") (pintype "passive"))
      (node (ref "U69") (pin "6") (pinfunction "IO3_6") (pintype "bidirectional"))
    )
    (net (code "45") (name "LED_DEBUG_3") (class "Default")
      (node (ref "R19") (pin "1") (pinfunction "1_1") (pintype "passive"))
      (node (ref "U69") (pin "5") (pinfunction "IO2_5") (pintype "bidirectional"))
    )
    (net (code "46") (name "LED_DEBUG_4") (class "Default")
      (node (ref "R20") (pin "1") (pinfunction "1_1") (pintype "passive"))
      (node (ref "U69") (pin "4") (pinfunction "IO1_4") (pintype "bidirectional"))
    )
    (net (code "47") (name "M1_M+") (class "Default")
      (node (ref "CR1") (pin "4") (pinfunction "OUT1_4") (pintype "output"))
      (node (ref "D11") (pin "1") (pinfunction "K_1") (pintype "bidirectional"))
      (node (ref "SV2") (pin "1") (pinfunction "1_1") (pintype "passive"))
      (node (ref "YRMOM") (pin "2") (pinfunction "A_2") (pintype "bidirectional"))
    )
    (net (code "48") (name "M1_M-") (class "Default")
      (node (ref "CR1") (pin "5") (pinfunction "OUT2_5") (pintype "output"))
      (node (ref "D10") (pin "1") (pinfunction "K_1") (pintype "bidirectional"))
      (node (ref "D8") (pin "2") (pinfunction "A_2") (pintype "bidirectional"))
      (node (ref "SV2") (pin "2") (pinfunction "2_2") (pintype "passive"))
    )
    (net (code "49") (name "M2_M+") (class "Default")
      (node (ref "CR1") (pin "16") (pinfunction "OUT3_16") (pintype "output"))
      (node (ref "D16") (pin "2") (pinfunction "A_2") (pintype "bidirectional"))
      (node (ref "D18") (pin "1") (pinfunction "K_1") (pintype "bidirectional"))
      (node (ref "SV4") (pin "1") (pinfunction "1_1") (pintype "passive"))
    )
    (net (code "50") (name "M2_M-") (class "Default")
      (node (ref "CR1") (pin "17") (pinfunction "OUT4_17") (pintype "output"))
      (node (ref "D17") (pin "2") (pinfunction "A_2") (pintype "bidirectional"))
      (node (ref "D19") (pin "1") (pinfunction "K_1") (pintype "bidirectional"))
      (node (ref "SV4") (pin "2") (pinfunction "2_2") (pintype "passive"))
    )
    (net (code "51") (name "MISO") (class "Default")
      (node (ref "JP1") (pin "3") (pinfunction "3_3") (pintype "passive"))
      (node (ref "U$2") (pin "P8") (pinfunction "SDO_P8") (pintype "bidirectional"))
      (node (ref "U69") (pin "31") (pinfunction "IO37_31") (pintype "bidirectional"))
    )
    (net (code "52") (name "MOSI") (class "Default")
      (node (ref "JP1") (pin "2") (pinfunction "2_2") (pintype "passive"))
      (node (ref "U$2") (pin "P5") (pinfunction "SDA_P5") (pintype "bidirectional"))
      (node (ref "U69") (pin "29") (pinfunction "IO35_29") (pintype "bidirectional"))
    )
    (net (code "53") (name "Net-(C1-Pad2)") (class "Default")
      (node (ref "C1") (pin "2") (pinfunction "2_2") (pintype "passive"))
      (node (ref "C6") (pin "2") (pinfunction "2_2") (pintype "passive"))
      (node (ref "C7") (pin "2") (pinfunction "2_2") (pintype "passive"))
      (node (ref "Q6") (pin "1") (pinfunction "D_1") (pintype "passive"))
      (node (ref "Q6") (pin "2") (pinfunction "D_2") (pintype "passive"))
      (node (ref "Q6") (pin "5") (pinfunction "D_5") (pintype "passive"))
      (node (ref "Q6") (pin "6") (pinfunction "D_6") (pintype "passive"))
      (node (ref "SENSOR_FRONT") (pin "3") (pinfunction "3_3") (pintype "passive"))
      (node (ref "SENSOR_LEFT") (pin "3") (pinfunction "3_3") (pintype "passive"))
      (node (ref "SENSOR_RIGHT") (pin "3") (pinfunction "3_3") (pintype "passive"))
    )
    (net (code "54") (name "Net-(D2-PadA)") (class "Default")
      (node (ref "D2") (pin "A") (pinfunction "A_A") (pintype "passive"))
      (node (ref "R1") (pin "2") (pinfunction "2_2") (pintype "passive"))
    )
    (net (code "55") (name "Net-(D3-PadA)") (class "Default")
      (node (ref "D3") (pin "A") (pinfunction "A_A") (pintype "passive"))
      (node (ref "R18") (pin "2") (pinfunction "2_2") (pintype "passive"))
    )
    (net (code "56") (name "Net-(D4-PadA)") (class "Default")
      (node (ref "D4") (pin "A") (pinfunction "A_A") (pintype "passive"))
      (node (ref "R19") (pin "2") (pinfunction "2_2") (pintype "passive"))
    )
    (net (code "57") (name "Net-(D5-PadA)") (class "Default")
      (node (ref "D5") (pin "A") (pinfunction "A_A") (pintype "passive"))
      (node (ref "R20") (pin "2") (pinfunction "2_2") (pintype "passive"))
    )
    (net (code "58") (name "Net-(D6-PadA)") (class "Default")
      (node (ref "D6") (pin "A") (pinfunction "A_A") (pintype "passive"))
      (node (ref "R21") (pin "1") (pinfunction "1_1") (pintype "passive"))
    )
    (net (code "59") (name "Net-(D7-PadA)") (class "Default")
      (node (ref "D7") (pin "A") (pinfunction "A_A") (pintype "passive"))
      (node (ref "R26") (pin "1") (pinfunction "1_1") (pintype "passive"))
    )
    (net (code "60") (name "Net-(D12-K)") (class "Default")
      (node (ref "D12") (pin "1") (pinfunction "K_1") (pintype "bidirectional"))
      (node (ref "IC1") (pin "2") (pinfunction "OUTPUT_2") (pintype "bidirectional"))
      (node (ref "L2") (pin "1") (pinfunction "1_1") (pintype "bidirectional"))
    )
    (net (code "61") (name "Net-(Q2-G)") (class "Default")
      (node (ref "Q2") (pin "1") (pinfunction "G_1") (pintype "passive"))
      (node (ref "R3") (pin "2") (pinfunction "2_2") (pintype "passive"))
    )
    (net (code "62") (name "Net-(Q3-D)") (class "Default")
      (node (ref "Q3") (pin "3") (pinfunction "D_3") (pintype "passive"))
      (node (ref "Q6") (pin "3") (pinfunction "G_3") (pintype "passive"))
      (node (ref "R25") (pin "1") (pinfunction "1_1") (pintype "passive"))
    )
    (net (code "63") (name "Net-(Q4-G)") (class "Default")
      (node (ref "Q4") (pin "1") (pinfunction "G_1") (pintype "passive"))
      (node (ref "R4") (pin "2") (pinfunction "2_2") (pintype "passive"))
    )
    (net (code "64") (name "Net-(S3-S)") (class "Default")
      (node (ref "S3") (pin "1") (pinfunction "S_1") (pintype "passive"))
      (node (ref "S3") (pin "2") (pinfunction "S1_2") (pintype "passive"))
      (node (ref "U69") (pin "11") (pinfunction "IO8_11") (pintype "bidirectional"))
    )
    (net (code "65") (name "Net-(U6A-IN+)") (class "Default")
      (node (ref "R5") (pin "1") (pinfunction "1_1") (pintype "passive"))
      (node (ref "R6") (pin "2") (pinfunction "2_2") (pintype "passive"))
      (node (ref "U6") (pin "3") (pinfunction "IN+_3") (pintype "input"))
    )
    (net (code "66") (name "RTS") (class "Default")
      (node (ref "JP4") (pin "1") (pinfunction "1_1") (pintype "passive"))
      (node (ref "Q2") (pin "2") (pinfunction "S_2") (pintype "passive"))
      (node (ref "R4") (pin "1") (pinfunction "1_1") (pintype "passive"))
      (node (ref "U2") (pin "14") (pinfunction "~{RTS}_14") (pintype "output"))
    )
    (net (code "67") (name "SENSOR_EN") (class "Default")
      (node (ref "Q3") (pin "1") (pinfunction "G_1") (pintype "passive"))
      (node (ref "U69") (pin "15") (pinfunction "IO12_15") (pintype "bidirectional"))
    )
    (net (code "68") (name "SENSOR_FRONT") (class "Default")
      (node (ref "SENSOR_FRONT") (pin "1") (pinfunction "1_1") (pintype "passive"))
      (node (ref "U69") (pin "13") (pinfunction "IO10_13") (pintype "bidirectional"))
    )
    (net (code "69") (name "SENSOR_LEFT") (class "Default")
      (node (ref "SENSOR_LEFT") (pin "1") (pinfunction "1_1") (pintype "passive"))
      (node (ref "U69") (pin "12") (pinfunction "IO9_12") (pintype "bidirectional"))
    )
    (net (code "70") (name "SENSOR_RIGHT") (class "Default")
      (node (ref "SENSOR_RIGHT") (pin "1") (pinfunction "1_1") (pintype "passive"))
      (node (ref "U69") (pin "14") (pinfunction "IO11_14") (pintype "bidirectional"))
    )
    (net (code "71") (name "USB_VBUS") (class "Default")
      (node (ref "D1") (pin "2") (pinfunction "2_2") (pintype "passive"))
      (node (ref "IC1") (pin "4") (pinfunction "SD_4") (pintype "bidirectional"))
      (node (ref "J1") (pin "1") (pinfunction "1_1") (pintype "bidirectional"))
      (node (ref "Q7") (pin "1") (pinfunction "D_1") (pintype "passive"))
      (node (ref "Q7") (pin "2") (pinfunction "D_2") (pintype "passive"))
      (node (ref "Q7") (pin "5") (pinfunction "D_5") (pintype "passive"))
      (node (ref "Q7") (pin "6") (pinfunction "D_6") (pintype "passive"))
      (node (ref "R2") (pin "2") (pinfunction "2_2") (pintype "passive"))
    )
    (net (code "72") (name "VBAT") (class "Default")
      (node (ref "C12") (pin "1") (pinfunction "1_1") (pintype "passive"))
      (node (ref "C9") (pin "1") (pinfunction "1_1") (pintype "passive"))
      (node (ref "CR1") (pin "6") (pinfunction "VS_6") (pintype "power_in"))
      (node (ref "D16") (pin "1") (pinfunction "K_1") (pintype "bidirectional"))
      (node (ref "D17") (pin "1") (pinfunction "K_1") (pintype "bidirectional"))
      (node (ref "D8") (pin "1") (pinfunction "K_1") (pintype "bidirectional"))
      (node (ref "IC1") (pin "1") (pinfunction "VIN_1") (pintype "bidirectional"))
      (node (ref "R16") (pin "2") (pinfunction "2_2") (pintype "passive"))
      (node (ref "R5") (pin "2") (pinfunction "2_2") (pintype "passive"))
      (node (ref "U$4") (pin "P+") (pinfunction "+_P+") (pintype "passive"))
      (node (ref "YRMOM") (pin "1") (pinfunction "K_1") (pintype "bidirectional"))
    )
    (net (code "73") (name "VSENSE_BAT") (class "Default")
      (node (ref "C18") (pin "1") (pinfunction "1_1") (pintype "passive"))
      (node (ref "R16") (pin "1") (pinfunction "1_1") (pintype "passive"))
      (node (ref "R17") (pin "2") (pinfunction "2_2") (pintype "passive"))
      (node (ref "U69") (pin "8") (pinfunction "IO5_8") (pintype "bidirectional"))
    )
    (net (code "74") (name "unconnected-(CR1-NC-Pad18)") (class "Default")
      (node (ref "CR1") (pin "18") (pinfunction "NC_18") (pintype "no_connect"))
    )
    (net (code "75") (name "unconnected-(CR1-NC_2-Pad3)") (class "Default")
      (node (ref "CR1") (pin "3") (pinfunction "NC_2_3") (pintype "no_connect"))
    )
    (net (code "76") (name "unconnected-(J1-PadMH1)") (class "Default")
      (node (ref "J1") (pin "MH1") (pinfunction "MH1_MH1") (pintype "bidirectional"))
    )
    (net (code "77") (name "unconnected-(J1-PadMH2)") (class "Default")
      (node (ref "J1") (pin "MH2") (pinfunction "MH2_MH2") (pintype "bidirectional"))
    )
    (net (code "78") (name "unconnected-(JP5-Pad2)") (class "Default")
      (node (ref "JP5") (pin "2") (pinfunction "2_2") (pintype "passive"))
    )
    (net (code "79") (name "unconnected-(JP5-Pad10)") (class "Default")
      (node (ref "JP5") (pin "10") (pinfunction "10_10") (pintype "passive"))
    )
    (net (code "80") (name "unconnected-(U$2-1V8-PadP2)") (class "Default")
      (node (ref "U$2") (pin "P2") (pinfunction "1V8_P2") (pintype "bidirectional"))
    )
    (net (code "81") (name "unconnected-(U$2-AC-PadP10)") (class "Default")
      (node (ref "U$2") (pin "P10") (pinfunction "AC_P10") (pintype "bidirectional"))
    )
    (net (code "82") (name "unconnected-(U$2-AD-PadP11)") (class "Default")
      (node (ref "U$2") (pin "P11") (pinfunction "AD_P11") (pintype "bidirectional"))
    )
    (net (code "83") (name "unconnected-(U$2-FS-PadP12)") (class "Default")
      (node (ref "U$2") (pin "P12") (pinfunction "FS_P12") (pintype "bidirectional"))
    )
    (net (code "84") (name "unconnected-(U2-NC.-Pad7)") (class "Default")
      (node (ref "U2") (pin "7") (pinfunction "NC._7") (pintype "no_connect"))
    )
    (net (code "85") (name "unconnected-(U2-R232-Pad15)") (class "Default")
      (node (ref "U2") (pin "15") (pinfunction "R232_15") (pintype "input"))
    )
    (net (code "86") (name "unconnected-(U2-~{CTS}-Pad9)") (class "Default")
      (node (ref "U2") (pin "9") (pinfunction "~{CTS}_9") (pintype "input"))
    )
    (net (code "87") (name "unconnected-(U2-~{DCD}-Pad12)") (class "Default")
      (node (ref "U2") (pin "12") (pinfunction "~{DCD}_12") (pintype "input"))
    )
    (net (code "88") (name "unconnected-(U2-~{DSR}-Pad10)") (class "Default")
      (node (ref "U2") (pin "10") (pinfunction "~{DSR}_10") (pintype "input"))
    )
    (net (code "89") (name "unconnected-(U2-~{OUT}-Pad8)") (class "Default")
      (node (ref "U2") (pin "8") (pinfunction "~{OUT}_8") (pintype "output"))
    )
    (net (code "90") (name "unconnected-(U2-~{RI}-Pad11)") (class "Default")
      (node (ref "U2") (pin "11") (pinfunction "~{RI}_11") (pintype "input"))
    )
    (net (code "91") (name "unconnected-(U6B-OUT-Pad7)") (class "Default")
      (node (ref "U6") (pin "7") (pinfunction "OUT_7") (pintype "output"))
    )
    (net (code "92") (name "{slash}VBUS_EN") (class "Default")
      (node (ref "Q7") (pin "3") (pinfunction "G_3") (pintype "passive"))
      (node (ref "U6") (pin "1") (pinfunction "OUT_1") (pintype "output"))
    )
  )
)
